# Patch-Prop1.net
KiCad netlist of a schematic drawn in EAGLE
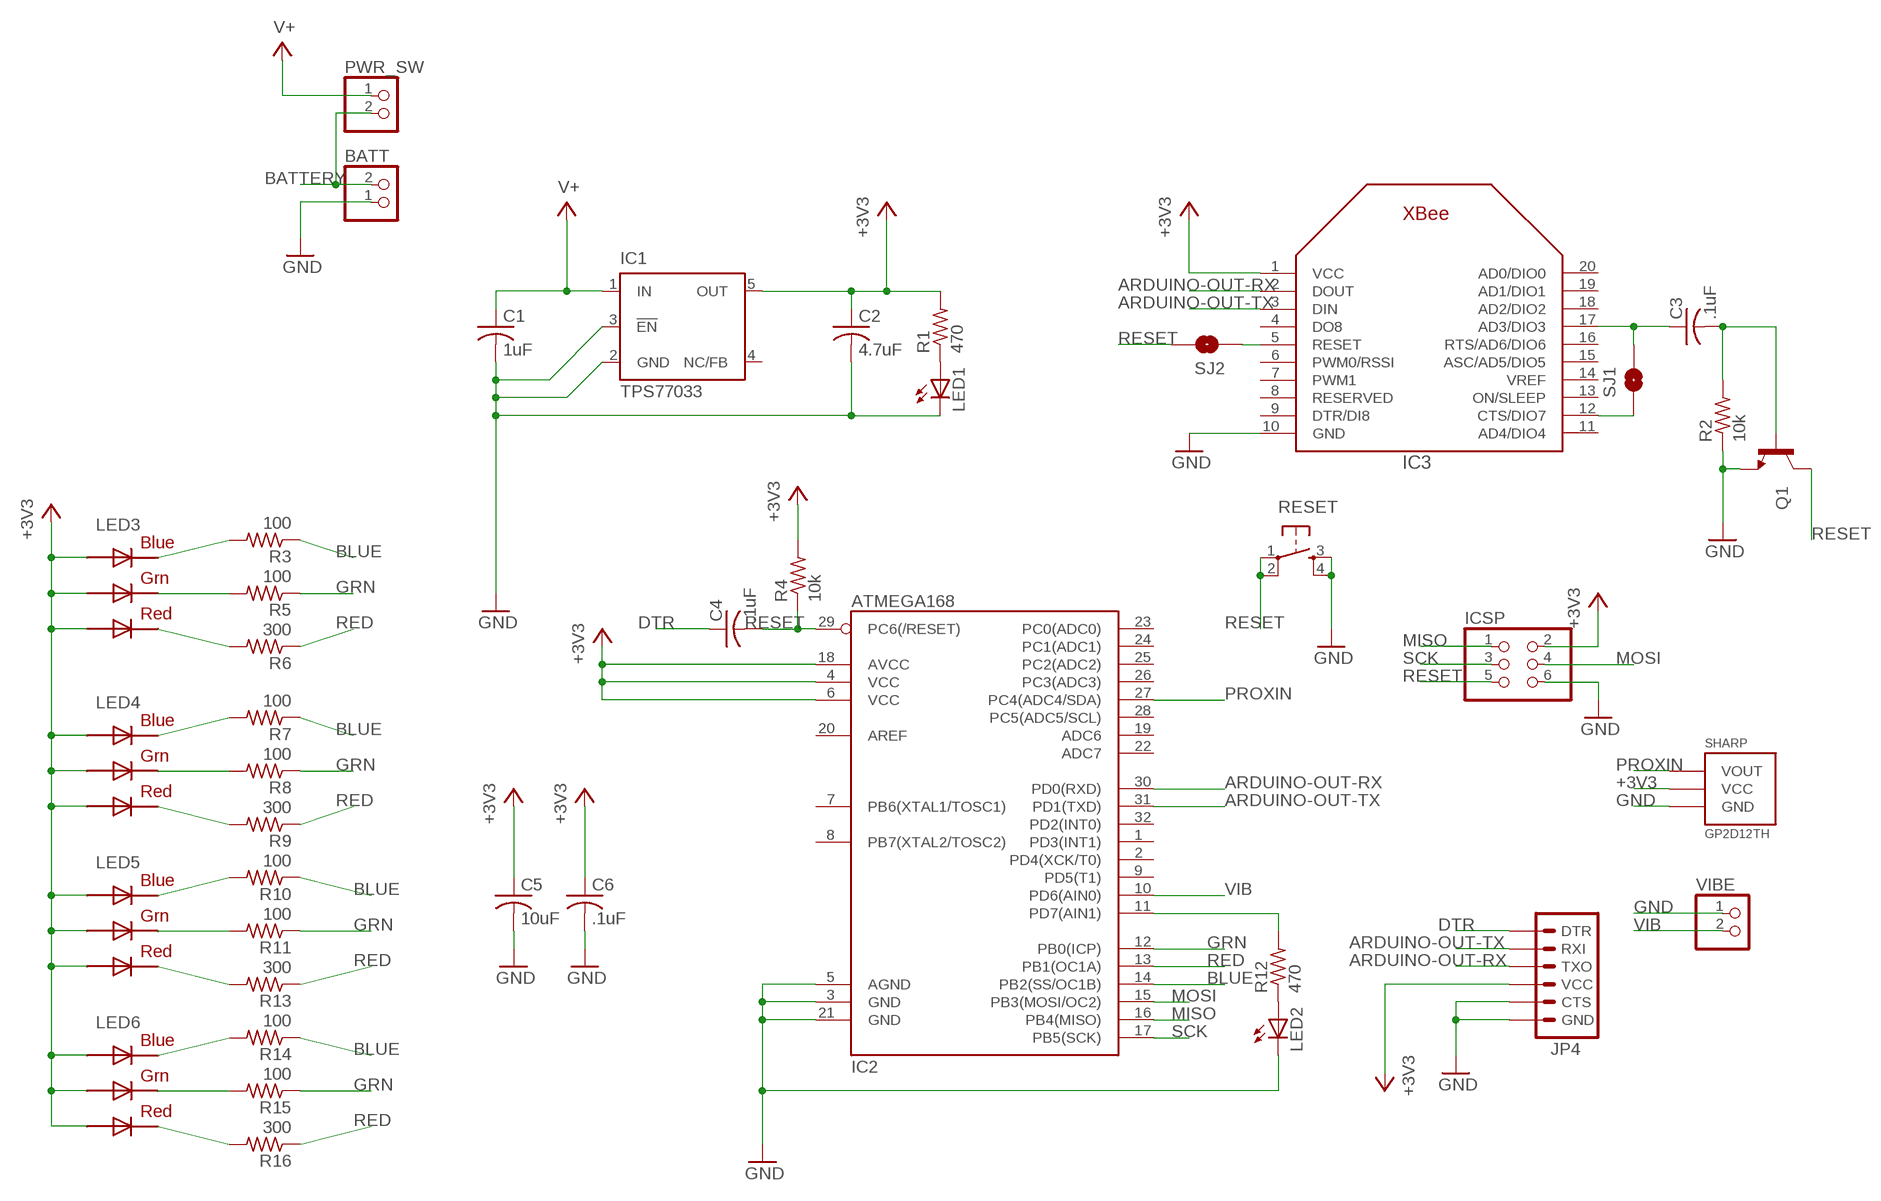
[diagram p0: schematic, sheet 1]

(export (version "E")
  (design (tool "Eeschema 10.0.6"))
  (components
    (comp (ref "BATT")
      (value "JST_2PIN-SMT-RA")
      (footprint "eagle-import:JST-PH-2-SMT-RA")
      (libsource (lib "eagle-import") (part "JST_2PIN-SMT-RA"))
    )
    (comp (ref "C1")
      (value "1uF")
      (footprint "eagle-import:C0603")
      (libsource (lib "eagle-import") (part "C-USC0603"))
    )
    (comp (ref "C2")
      (value "4.7uF")
      (footprint "eagle-import:C0603")
      (libsource (lib "eagle-import") (part "C-USC0603"))
    )
    (comp (ref "C3")
      (value ".1uF")
      (footprint "eagle-import:C0603")
      (libsource (lib "eagle-import") (part "C-USC0603"))
    )
    (comp (ref "C4")
      (value ".1uF")
      (footprint "eagle-import:C0603")
      (libsource (lib "eagle-import") (part "C-USC0603"))
    )
    (comp (ref "C5")
      (value "10uF")
      (footprint "eagle-import:C0603")
      (libsource (lib "eagle-import") (part "C-USC0603"))
    )
    (comp (ref "C6")
      (value ".1uF")
      (footprint "eagle-import:C0603")
      (libsource (lib "eagle-import") (part "C-USC0603"))
    )
    (comp (ref "IC1")
      (value "TPS77033")
      (footprint "eagle-import:SOT23-DBV")
      (fields (field (name "MF") "TEXAS INSTRUMENTS") (field (name "MPN") "TPS77033DBVT"))
      (libsource (lib "eagle-import") (part "TPS77033"))
    )
    (comp (ref "IC2")
      (value "ATMEGA168")
      (footprint "eagle-import:TQFP32-08")
      (libsource (lib "eagle-import") (part "ATMEGA168"))
    )
    (comp (ref "IC3")
      (value "XBEE")
      (footprint "eagle-import:XBEE")
      (libsource (lib "eagle-import") (part "XBEE"))
    )
    (comp (ref "ICSP")
      (value "PINHD-2X3")
      (footprint "eagle-import:2X03")
      (libsource (lib "eagle-import") (part "PINHD-2X3"))
    )
    (comp (ref "JP4")
      (value "ARDUINO_SERIAL_PROGRAMSMD")
      (footprint "eagle-import:1X06-SMD")
      (libsource (lib "eagle-import") (part "ARDUINO_SERIAL_PROGRAMSMD"))
    )
    (comp (ref "LED1")
      (value "LEDCHIPLED_0805")
      (footprint "eagle-import:CHIPLED_0805")
      (libsource (lib "eagle-import") (part "LEDCHIPLED_0805"))
    )
    (comp (ref "LED2")
      (value "LEDCHIPLED_0805")
      (footprint "eagle-import:CHIPLED_0805")
      (libsource (lib "eagle-import") (part "LEDCHIPLED_0805"))
    )
    (comp (ref "LED3")
      (value "RGBLED5050")
      (footprint "eagle-import:RGBLED5050")
      (libsource (lib "eagle-import") (part "RGBLED5050"))
    )
    (comp (ref "LED4")
      (value "RGBLED5050")
      (footprint "eagle-import:RGBLED5050")
      (libsource (lib "eagle-import") (part "RGBLED5050"))
    )
    (comp (ref "LED5")
      (value "RGBLED5050")
      (footprint "eagle-import:RGBLED5050")
      (libsource (lib "eagle-import") (part "RGBLED5050"))
    )
    (comp (ref "LED6")
      (value "RGBLED5050")
      (footprint "eagle-import:RGBLED5050")
      (libsource (lib "eagle-import") (part "RGBLED5050"))
    )
    (comp (ref "PWR_SW")
      (value "PINHD-1X2")
      (footprint "eagle-import:1X02")
      (libsource (lib "eagle-import") (part "PINHD-1X2"))
    )
    (comp (ref "Q1")
      (value "TRANSISTOR_NPNSOT89")
      (footprint "eagle-import:SOT89")
      (libsource (lib "eagle-import") (part "TRANSISTOR_NPNSOT89"))
    )
    (comp (ref "R1")
      (value "470")
      (footprint "eagle-import:R0603")
      (libsource (lib "eagle-import") (part "R-US_R0603"))
    )
    (comp (ref "R2")
      (value "10k")
      (footprint "eagle-import:R0603")
      (libsource (lib "eagle-import") (part "R-US_R0603"))
    )
    (comp (ref "R3")
      (value "100")
      (footprint "eagle-import:R0603")
      (libsource (lib "eagle-import") (part "R-US_R0603"))
    )
    (comp (ref "R4")
      (value "10k")
      (footprint "eagle-import:R0603")
      (libsource (lib "eagle-import") (part "R-US_R0603"))
    )
    (comp (ref "R5")
      (value "100")
      (footprint "eagle-import:R0603")
      (libsource (lib "eagle-import") (part "R-US_R0603"))
    )
    (comp (ref "R6")
      (value "300")
      (footprint "eagle-import:R0603")
      (libsource (lib "eagle-import") (part "R-US_R0603"))
    )
    (comp (ref "R7")
      (value "100")
      (footprint "eagle-import:R0603")
      (libsource (lib "eagle-import") (part "R-US_R0603"))
    )
    (comp (ref "R8")
      (value "100")
      (footprint "eagle-import:R0603")
      (libsource (lib "eagle-import") (part "R-US_R0603"))
    )
    (comp (ref "R9")
      (value "300")
      (footprint "eagle-import:R0603")
      (libsource (lib "eagle-import") (part "R-US_R0603"))
    )
    (comp (ref "R10")
      (value "100")
      (footprint "eagle-import:R0603")
      (libsource (lib "eagle-import") (part "R-US_R0603"))
    )
    (comp (ref "R11")
      (value "100")
      (footprint "eagle-import:R0603")
      (libsource (lib "eagle-import") (part "R-US_R0603"))
    )
    (comp (ref "R12")
      (value "470")
      (footprint "eagle-import:R0603")
      (libsource (lib "eagle-import") (part "R-US_R0603"))
    )
    (comp (ref "R13")
      (value "300")
      (footprint "eagle-import:R0603")
      (libsource (lib "eagle-import") (part "R-US_R0603"))
    )
    (comp (ref "R14")
      (value "100")
      (footprint "eagle-import:R0603")
      (libsource (lib "eagle-import") (part "R-US_R0603"))
    )
    (comp (ref "R15")
      (value "100")
      (footprint "eagle-import:R0603")
      (libsource (lib "eagle-import") (part "R-US_R0603"))
    )
    (comp (ref "R16")
      (value "300")
      (footprint "eagle-import:R0603")
      (libsource (lib "eagle-import") (part "R-US_R0603"))
    )
    (comp (ref "RESET")
      (value "TAC_SWITCHPTH")
      (footprint "eagle-import:TACTILE-PTH")
      (libsource (lib "eagle-import") (part "TAC_SWITCHPTH"))
    )
    (comp (ref "SHARP")
      (value "GP2D12TH")
      (footprint "eagle-import:GP2D12")
      (libsource (lib "eagle-import") (part "GP2D12TH"))
    )
    (comp (ref "SJ1")
      (value "SOLDERJUMPERNO")
      (footprint "eagle-import:SJ_2S-NO")
      (libsource (lib "eagle-import") (part "SOLDERJUMPERNO"))
    )
    (comp (ref "SJ2")
      (value "SOLDERJUMPERNO")
      (footprint "eagle-import:SJ_2S-NO")
      (libsource (lib "eagle-import") (part "SOLDERJUMPERNO"))
    )
    (comp (ref "VIBE")
      (value "PINHD-1X2")
      (footprint "eagle-import:1X02")
      (libsource (lib "eagle-import") (part "PINHD-1X2"))
    )
  )
  (nets
    (net (code "1") (name "+3V3") (class "Default")
      (node (ref "C2") (pin "1") (pinfunction "1_1") (pintype "passive"))
      (node (ref "C5") (pin "1") (pinfunction "1_1") (pintype "passive"))
      (node (ref "C6") (pin "1") (pinfunction "1_1") (pintype "passive"))
      (node (ref "IC1") (pin "5") (pinfunction "OUT_5") (pintype "passive"))
      (node (ref "IC2") (pin "18") (pinfunction "AVCC_18") (pintype "bidirectional"))
      (node (ref "IC2") (pin "4") (pinfunction "VCC_4") (pintype "bidirectional"))
      (node (ref "IC2") (pin "6") (pinfunction "VCC_6") (pintype "bidirectional"))
      (node (ref "IC3") (pin "1") (pinfunction "VCC_1") (pintype "power_in"))
      (node (ref "ICSP") (pin "2") (pinfunction "2_2") (pintype "passive"))
      (node (ref "JP4") (pin "4") (pinfunction "VCC_4") (pintype "passive"))
      (node (ref "LED3") (pin "1") (pinfunction "GREEN_A_1") (pintype "bidirectional"))
      (node (ref "LED3") (pin "2") (pinfunction "RED_A_2") (pintype "bidirectional"))
      (node (ref "LED3") (pin "3") (pinfunction "BLUE_A_3") (pintype "bidirectional"))
      (node (ref "LED4") (pin "1") (pinfunction "GREEN_A_1") (pintype "bidirectional"))
      (node (ref "LED4") (pin "2") (pinfunction "RED_A_2") (pintype "bidirectional"))
      (node (ref "LED4") (pin "3") (pinfunction "BLUE_A_3") (pintype "bidirectional"))
      (node (ref "LED5") (pin "1") (pinfunction "GREEN_A_1") (pintype "bidirectional"))
      (node (ref "LED5") (pin "2") (pinfunction "RED_A_2") (pintype "bidirectional"))
      (node (ref "LED5") (pin "3") (pinfunction "BLUE_A_3") (pintype "bidirectional"))
      (node (ref "LED6") (pin "1") (pinfunction "GREEN_A_1") (pintype "bidirectional"))
      (node (ref "LED6") (pin "2") (pinfunction "RED_A_2") (pintype "bidirectional"))
      (node (ref "LED6") (pin "3") (pinfunction "BLUE_A_3") (pintype "bidirectional"))
      (node (ref "R1") (pin "2") (pinfunction "2_2") (pintype "passive"))
      (node (ref "R4") (pin "2") (pinfunction "2_2") (pintype "passive"))
      (node (ref "SHARP") (pin "VCC") (pinfunction "VCC_VCC") (pintype "power_in"))
    )
    (net (code "2") (name "/ARDUINO-OUT-RX") (class "Default")
      (node (ref "IC2") (pin "30") (pinfunction "PD0(RXD)_30") (pintype "bidirectional"))
      (node (ref "IC3") (pin "2") (pinfunction "DOUT_2") (pintype "output"))
      (node (ref "JP4") (pin "3") (pinfunction "TXO_3") (pintype "passive"))
    )
    (net (code "3") (name "/ARDUINO-OUT-TX") (class "Default")
      (node (ref "IC2") (pin "31") (pinfunction "PD1(TXD)_31") (pintype "bidirectional"))
      (node (ref "IC3") (pin "3") (pinfunction "DIN_3") (pintype "input"))
      (node (ref "JP4") (pin "2") (pinfunction "RXI_2") (pintype "passive"))
    )
    (net (code "4") (name "/BATTERY") (class "Default")
      (node (ref "BATT") (pin "2") (pinfunction "1_2") (pintype "passive"))
      (node (ref "PWR_SW") (pin "2") (pinfunction "2_2") (pintype "passive"))
    )
    (net (code "5") (name "/BLUE") (class "Default")
      (node (ref "IC2") (pin "14") (pinfunction "PB2(SS/OC1B)_14") (pintype "bidirectional"))
      (node (ref "R10") (pin "1") (pinfunction "1_1") (pintype "passive"))
      (node (ref "R14") (pin "1") (pinfunction "1_1") (pintype "passive"))
      (node (ref "R3") (pin "1") (pinfunction "1_1") (pintype "passive"))
      (node (ref "R7") (pin "1") (pinfunction "1_1") (pintype "passive"))
    )
    (net (code "6") (name "/DTR") (class "Default")
      (node (ref "C4") (pin "1") (pinfunction "1_1") (pintype "passive"))
      (node (ref "JP4") (pin "1") (pinfunction "DTR_1") (pintype "passive"))
    )
    (net (code "7") (name "/GRN") (class "Default")
      (node (ref "IC2") (pin "12") (pinfunction "PB0(ICP)_12") (pintype "bidirectional"))
      (node (ref "R11") (pin "1") (pinfunction "1_1") (pintype "passive"))
      (node (ref "R15") (pin "1") (pinfunction "1_1") (pintype "passive"))
      (node (ref "R5") (pin "1") (pinfunction "1_1") (pintype "passive"))
      (node (ref "R8") (pin "1") (pinfunction "1_1") (pintype "passive"))
    )
    (net (code "8") (name "/MISO") (class "Default")
      (node (ref "IC2") (pin "16") (pinfunction "PB4(MISO)_16") (pintype "bidirectional"))
      (node (ref "ICSP") (pin "1") (pinfunction "1_1") (pintype "passive"))
    )
    (net (code "9") (name "/MOSI") (class "Default")
      (node (ref "IC2") (pin "15") (pinfunction "PB3(MOSI/OC2)_15") (pintype "bidirectional"))
      (node (ref "ICSP") (pin "4") (pinfunction "4_4") (pintype "passive"))
    )
    (net (code "10") (name "/PROXIN") (class "Default")
      (node (ref "IC2") (pin "27") (pinfunction "PC4(ADC4/SDA)_27") (pintype "bidirectional"))
      (node (ref "SHARP") (pin "VOUT") (pinfunction "VOUT_VOUT") (pintype "output"))
    )
    (net (code "11") (name "/RED") (class "Default")
      (node (ref "IC2") (pin "13") (pinfunction "PB1(OC1A)_13") (pintype "bidirectional"))
      (node (ref "R13") (pin "1") (pinfunction "1_1") (pintype "passive"))
      (node (ref "R16") (pin "1") (pinfunction "1_1") (pintype "passive"))
      (node (ref "R6") (pin "1") (pinfunction "1_1") (pintype "passive"))
      (node (ref "R9") (pin "1") (pinfunction "1_1") (pintype "passive"))
    )
    (net (code "12") (name "/RESET") (class "Default")
      (node (ref "C4") (pin "2") (pinfunction "2_2") (pintype "passive"))
      (node (ref "IC2") (pin "29") (pinfunction "PC6(/RESET)_29") (pintype "bidirectional"))
      (node (ref "ICSP") (pin "5") (pinfunction "5_5") (pintype "passive"))
      (node (ref "Q1") (pin "2") (pinfunction "C_2") (pintype "passive"))
      (node (ref "R4") (pin "1") (pinfunction "1_1") (pintype "passive"))
      (node (ref "RESET") (pin "1") (pinfunction "1_1") (pintype "passive"))
      (node (ref "RESET") (pin "2") (pinfunction "2_2") (pintype "passive"))
      (node (ref "SJ2") (pin "2") (pinfunction "2_2") (pintype "passive"))
    )
    (net (code "13") (name "/SCK") (class "Default")
      (node (ref "IC2") (pin "17") (pinfunction "PB5(SCK)_17") (pintype "bidirectional"))
      (node (ref "ICSP") (pin "3") (pinfunction "3_3") (pintype "passive"))
    )
    (net (code "14") (name "/VIB") (class "Default")
      (node (ref "IC2") (pin "10") (pinfunction "PD6(AIN0)_10") (pintype "bidirectional"))
      (node (ref "VIBE") (pin "2") (pinfunction "2_2") (pintype "passive"))
    )
    (net (code "15") (name "GND") (class "Default")
      (node (ref "BATT") (pin "1") (pinfunction "2_1") (pintype "passive"))
      (node (ref "C1") (pin "2") (pinfunction "2_2") (pintype "passive"))
      (node (ref "C2") (pin "2") (pinfunction "2_2") (pintype "passive"))
      (node (ref "C5") (pin "2") (pinfunction "2_2") (pintype "passive"))
      (node (ref "C6") (pin "2") (pinfunction "2_2") (pintype "passive"))
      (node (ref "IC1") (pin "2") (pinfunction "GND_2") (pintype "power_in"))
      (node (ref "IC1") (pin "3") (pinfunction "~{EN}_3") (pintype "input"))
      (node (ref "IC2") (pin "21") (pinfunction "GND_21") (pintype "bidirectional"))
      (node (ref "IC2") (pin "3") (pinfunction "GND_3") (pintype "bidirectional"))
      (node (ref "IC2") (pin "5") (pinfunction "AGND_5") (pintype "bidirectional"))
      (node (ref "IC3") (pin "10") (pinfunction "GND_10") (pintype "power_in"))
      (node (ref "ICSP") (pin "6") (pinfunction "6_6") (pintype "passive"))
      (node (ref "JP4") (pin "5") (pinfunction "CTS_5") (pintype "passive"))
      (node (ref "JP4") (pin "6") (pinfunction "GND_6") (pintype "passive"))
      (node (ref "LED1") (pin "C") (pinfunction "C_C") (pintype "passive"))
      (node (ref "LED2") (pin "C") (pinfunction "C_C") (pintype "passive"))
      (node (ref "Q1") (pin "3") (pinfunction "E_3") (pintype "passive"))
      (node (ref "R2") (pin "1") (pinfunction "1_1") (pintype "passive"))
      (node (ref "RESET") (pin "3") (pinfunction "3_3") (pintype "passive"))
      (node (ref "RESET") (pin "4") (pinfunction "4_4") (pintype "passive"))
      (node (ref "SHARP") (pin "GND") (pinfunction "GND_GND") (pintype "power_in"))
      (node (ref "VIBE") (pin "1") (pinfunction "1_1") (pintype "passive"))
    )
    (net (code "16") (name "Net-(IC2-PD7(AIN1))") (class "Default")
      (node (ref "IC2") (pin "11") (pinfunction "PD7(AIN1)_11") (pintype "bidirectional"))
      (node (ref "R12") (pin "2") (pinfunction "2_2") (pintype "passive"))
    )
    (net (code "17") (name "Net-(IC3-AD3{slash}DIO3)") (class "Default")
      (node (ref "C3") (pin "1") (pinfunction "1_1") (pintype "passive"))
      (node (ref "IC3") (pin "17") (pinfunction "AD3/DIO3_17") (pintype "bidirectional"))
      (node (ref "SJ1") (pin "2") (pinfunction "2_2") (pintype "passive"))
    )
    (net (code "18") (name "Net-(IC3-CTS{slash}DIO7)") (class "Default")
      (node (ref "IC3") (pin "12") (pinfunction "CTS/DIO7_12") (pintype "bidirectional"))
      (node (ref "SJ1") (pin "1") (pinfunction "1_1") (pintype "passive"))
    )
    (net (code "19") (name "Net-(IC3-RESET)") (class "Default")
      (node (ref "IC3") (pin "5") (pinfunction "RESET_5") (pintype "input"))
      (node (ref "SJ2") (pin "1") (pinfunction "1_1") (pintype "passive"))
    )
    (net (code "20") (name "Net-(LED1-PadA)") (class "Default")
      (node (ref "LED1") (pin "A") (pinfunction "A_A") (pintype "passive"))
      (node (ref "R1") (pin "1") (pinfunction "1_1") (pintype "passive"))
    )
    (net (code "21") (name "Net-(LED2-PadA)") (class "Default")
      (node (ref "LED2") (pin "A") (pinfunction "A_A") (pintype "passive"))
      (node (ref "R12") (pin "1") (pinfunction "1_1") (pintype "passive"))
    )
    (net (code "22") (name "Net-(LED3-BLUE_C)") (class "Default")
      (node (ref "LED3") (pin "4") (pinfunction "BLUE_C_4") (pintype "bidirectional"))
      (node (ref "R3") (pin "2") (pinfunction "2_2") (pintype "passive"))
    )
    (net (code "23") (name "Net-(LED3-GREEN_C)") (class "Default")
      (node (ref "LED3") (pin "6") (pinfunction "GREEN_C_6") (pintype "bidirectional"))
      (node (ref "R5") (pin "2") (pinfunction "2_2") (pintype "passive"))
    )
    (net (code "24") (name "Net-(LED3-RED_C)") (class "Default")
      (node (ref "LED3") (pin "5") (pinfunction "RED_C_5") (pintype "bidirectional"))
      (node (ref "R6") (pin "2") (pinfunction "2_2") (pintype "passive"))
    )
    (net (code "25") (name "Net-(LED4-BLUE_C)") (class "Default")
      (node (ref "LED4") (pin "4") (pinfunction "BLUE_C_4") (pintype "bidirectional"))
      (node (ref "R7") (pin "2") (pinfunction "2_2") (pintype "passive"))
    )
    (net (code "26") (name "Net-(LED4-GREEN_C)") (class "Default")
      (node (ref "LED4") (pin "6") (pinfunction "GREEN_C_6") (pintype "bidirectional"))
      (node (ref "R8") (pin "2") (pinfunction "2_2") (pintype "passive"))
    )
    (net (code "27") (name "Net-(LED4-RED_C)") (class "Default")
      (node (ref "LED4") (pin "5") (pinfunction "RED_C_5") (pintype "bidirectional"))
      (node (ref "R9") (pin "2") (pinfunction "2_2") (pintype "passive"))
    )
    (net (code "28") (name "Net-(LED5-BLUE_C)") (class "Default")
      (node (ref "LED5") (pin "4") (pinfunction "BLUE_C_4") (pintype "bidirectional"))
      (node (ref "R10") (pin "2") (pinfunction "2_2") (pintype "passive"))
    )
    (net (code "29") (name "Net-(LED5-GREEN_C)") (class "Default")
      (node (ref "LED5") (pin "6") (pinfunction "GREEN_C_6") (pintype "bidirectional"))
      (node (ref "R11") (pin "2") (pinfunction "2_2") (pintype "passive"))
    )
    (net (code "30") (name "Net-(LED5-RED_C)") (class "Default")
      (node (ref "LED5") (pin "5") (pinfunction "RED_C_5") (pintype "bidirectional"))
      (node (ref "R13") (pin "2") (pinfunction "2_2") (pintype "passive"))
    )
    (net (code "31") (name "Net-(LED6-BLUE_C)") (class "Default")
      (node (ref "LED6") (pin "4") (pinfunction "BLUE_C_4") (pintype "bidirectional"))
      (node (ref "R14") (pin "2") (pinfunction "2_2") (pintype "passive"))
    )
    (net (code "32") (name "Net-(LED6-GREEN_C)") (class "Default")
      (node (ref "LED6") (pin "6") (pinfunction "GREEN_C_6") (pintype "bidirectional"))
      (node (ref "R15") (pin "2") (pinfunction "2_2") (pintype "passive"))
    )
    (net (code "33") (name "Net-(LED6-RED_C)") (class "Default")
      (node (ref "LED6") (pin "5") (pinfunction "RED_C_5") (pintype "bidirectional"))
      (node (ref "R16") (pin "2") (pinfunction "2_2") (pintype "passive"))
    )
    (net (code "34") (name "Net-(Q1-B)") (class "Default")
      (node (ref "C3") (pin "2") (pinfunction "2_2") (pintype "passive"))
      (node (ref "Q1") (pin "1") (pinfunction "B_1") (pintype "passive"))
      (node (ref "R2") (pin "2") (pinfunction "2_2") (pintype "passive"))
    )
    (net (code "35") (name "V+") (class "Default")
      (node (ref "C1") (pin "1") (pinfunction "1_1") (pintype "passive"))
      (node (ref "IC1") (pin "1") (pinfunction "IN_1") (pintype "input"))
      (node (ref "PWR_SW") (pin "1") (pinfunction "1_1") (pintype "passive"))
    )
    (net (code "36") (name "unconnected-(IC1-NC{slash}FB-Pad4)") (class "Default")
      (node (ref "IC1") (pin "4") (pinfunction "NC/FB_4") (pintype "passive"))
    )
    (net (code "37") (name "unconnected-(IC2-ADC6-Pad19)") (class "Default")
      (node (ref "IC2") (pin "19") (pinfunction "ADC6_19") (pintype "bidirectional"))
    )
    (net (code "38") (name "unconnected-(IC2-ADC7-Pad22)") (class "Default")
      (node (ref "IC2") (pin "22") (pinfunction "ADC7_22") (pintype "bidirectional"))
    )
    (net (code "39") (name "unconnected-(IC2-AREF-Pad20)") (class "Default")
      (node (ref "IC2") (pin "20") (pinfunction "AREF_20") (pintype "bidirectional"))
    )
    (net (code "40") (name "unconnected-(IC2-PB6(XTAL1{slash}TOSC1)-Pad7)") (class "Default")
      (node (ref "IC2") (pin "7") (pinfunction "PB6(XTAL1/TOSC1)_7") (pintype "bidirectional"))
    )
    (net (code "41") (name "unconnected-(IC2-PB7(XTAL2{slash}TOSC2)-Pad8)") (class "Default")
      (node (ref "IC2") (pin "8") (pinfunction "PB7(XTAL2/TOSC2)_8") (pintype "bidirectional"))
    )
    (net (code "42") (name "unconnected-(IC2-PC0(ADC0)-Pad23)") (class "Default")
      (node (ref "IC2") (pin "23") (pinfunction "PC0(ADC0)_23") (pintype "bidirectional"))
    )
    (net (code "43") (name "unconnected-(IC2-PC1(ADC1)-Pad24)") (class "Default")
      (node (ref "IC2") (pin "24") (pinfunction "PC1(ADC1)_24") (pintype "bidirectional"))
    )
    (net (code "44") (name "unconnected-(IC2-PC2(ADC2)-Pad25)") (class "Default")
      (node (ref "IC2") (pin "25") (pinfunction "PC2(ADC2)_25") (pintype "bidirectional"))
    )
    (net (code "45") (name "unconnected-(IC2-PC3(ADC3)-Pad26)") (class "Default")
      (node (ref "IC2") (pin "26") (pinfunction "PC3(ADC3)_26") (pintype "bidirectional"))
    )
    (net (code "46") (name "unconnected-(IC2-PC5(ADC5{slash}SCL)-Pad28)") (class "Default")
      (node (ref "IC2") (pin "28") (pinfunction "PC5(ADC5/SCL)_28") (pintype "bidirectional"))
    )
    (net (code "47") (name "unconnected-(IC2-PD2(INT0)-Pad32)") (class "Default")
      (node (ref "IC2") (pin "32") (pinfunction "PD2(INT0)_32") (pintype "bidirectional"))
    )
    (net (code "48") (name "unconnected-(IC2-PD3(INT1)-Pad1)") (class "Default")
      (node (ref "IC2") (pin "1") (pinfunction "PD3(INT1)_1") (pintype "bidirectional"))
    )
    (net (code "49") (name "unconnected-(IC2-PD4(XCK{slash}T0)-Pad2)") (class "Default")
      (node (ref "IC2") (pin "2") (pinfunction "PD4(XCK/T0)_2") (pintype "bidirectional"))
    )
    (net (code "50") (name "unconnected-(IC2-PD5(T1)-Pad9)") (class "Default")
      (node (ref "IC2") (pin "9") (pinfunction "PD5(T1)_9") (pintype "bidirectional"))
    )
    (net (code "51") (name "unconnected-(IC3-AD0{slash}DIO0-Pad20)") (class "Default")
      (node (ref "IC3") (pin "20") (pinfunction "AD0/DIO0_20") (pintype "bidirectional"))
    )
    (net (code "52") (name "unconnected-(IC3-AD1{slash}DIO1-Pad19)") (class "Default")
      (node (ref "IC3") (pin "19") (pinfunction "AD1/DIO1_19") (pintype "bidirectional"))
    )
    (net (code "53") (name "unconnected-(IC3-AD2{slash}DIO2-Pad18)") (class "Default")
      (node (ref "IC3") (pin "18") (pinfunction "AD2/DIO2_18") (pintype "bidirectional"))
    )
    (net (code "54") (name "unconnected-(IC3-AD4{slash}DIO4-Pad11)") (class "Default")
      (node (ref "IC3") (pin "11") (pinfunction "AD4/DIO4_11") (pintype "bidirectional"))
    )
    (net (code "55") (name "unconnected-(IC3-ASC{slash}AD5{slash}DIO5-Pad15)") (class "Default")
      (node (ref "IC3") (pin "15") (pinfunction "ASC/AD5/DIO5_15") (pintype "bidirectional"))
    )
    (net (code "56") (name "unconnected-(IC3-DO8-Pad4)") (class "Default")
      (node (ref "IC3") (pin "4") (pinfunction "DO8_4") (pintype "output"))
    )
    (net (code "57") (name "unconnected-(IC3-DTR{slash}DI8-Pad9)") (class "Default")
      (node (ref "IC3") (pin "9") (pinfunction "DTR/DI8_9") (pintype "input"))
    )
    (net (code "58") (name "unconnected-(IC3-ON{slash}SLEEP-Pad13)") (class "Default")
      (node (ref "IC3") (pin "13") (pinfunction "ON/SLEEP_13") (pintype "output"))
    )
    (net (code "59") (name "unconnected-(IC3-PWM0{slash}RSSI-Pad6)") (class "Default")
      (node (ref "IC3") (pin "6") (pinfunction "PWM0/RSSI_6") (pintype "output"))
    )
    (net (code "60") (name "unconnected-(IC3-PWM1-Pad7)") (class "Default")
      (node (ref "IC3") (pin "7") (pinfunction "PWM1_7") (pintype "output"))
    )
    (net (code "61") (name "unconnected-(IC3-RESERVED-Pad8)") (class "Default")
      (node (ref "IC3") (pin "8") (pinfunction "RESERVED_8") (pintype "no_connect"))
    )
    (net (code "62") (name "unconnected-(IC3-RTS{slash}AD6{slash}DIO6-Pad16)") (class "Default")
      (node (ref "IC3") (pin "16") (pinfunction "RTS/AD6/DIO6_16") (pintype "bidirectional"))
    )
    (net (code "63") (name "unconnected-(IC3-VREF-Pad14)") (class "Default")
      (node (ref "IC3") (pin "14") (pinfunction "VREF_14") (pintype "input"))
    )
  )
)
